# Sheet1.net
KiCad netlist of a schematic drawn in Altium Designer
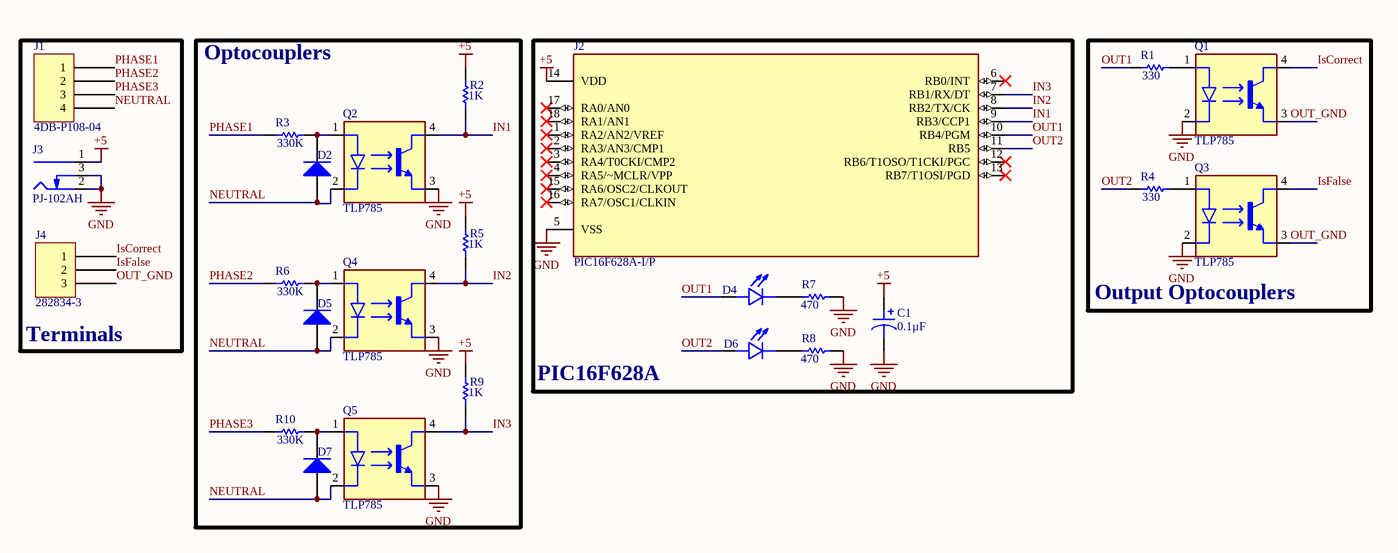
[diagram p0: Sheet1.SchDoc]

(export (version "E")
  (design (tool "Eeschema 10.0.6"))
  (components
    (comp (ref "C1")
      (value "0.1µF")
      (footprint "CAP TH ALUM ELEC D5.00mm S2.00mm H12.00mm")
      (description "CAP ALUM 0.1UF 10% 100V RADIAL")
      (fields (field (name "PART NUMBER") "UKL2A0R1KDD") (field (name "MANUFACTURER") "Nichicon"))
      (libsource (lib "Celestial Altium Library - altium_library") (part "Polarised Capacitor"))
    )
    (comp (ref "D2")
      (value "Diode 1N4007")
      (footprint "DO-41")
      (description "1 Amp General Purpose Rectifier")
      (fields (field (name "PUBLISHER") "Altium Limited"))
      (libsource (lib "Miscellaneous Devices") (part "Diode 1N4007"))
    )
    (comp (ref "D4")
      (value "HLMP-4719-A00B2")
      (footprint "LEDRD254W47D584H1078")
      (description "Yellow 5mm LED LOW CURRENT 2mA R/A T/L")
      (fields (field (name "MF") "Avago"))
      (libsource (lib "5mmLED") (part "HLMP-4719-A00B2"))
    )
    (comp (ref "D5")
      (value "Diode 1N4007")
      (footprint "DO-41")
      (description "1 Amp General Purpose Rectifier")
      (fields (field (name "PUBLISHER") "Altium Limited"))
      (libsource (lib "Miscellaneous Devices") (part "Diode 1N4007"))
    )
    (comp (ref "D6")
      (value "HLMP-4719-A00B2")
      (footprint "LEDRD254W47D584H1078")
      (description "Yellow 5mm LED LOW CURRENT 2mA R/A T/L")
      (fields (field (name "MF") "Avago"))
      (libsource (lib "5mmLED") (part "HLMP-4719-A00B2"))
    )
    (comp (ref "D7")
      (value "Diode 1N4007")
      (footprint "DO-41")
      (description "1 Amp General Purpose Rectifier")
      (fields (field (name "PUBLISHER") "Altium Limited"))
      (libsource (lib "Miscellaneous Devices") (part "Diode 1N4007"))
    )
    (comp (ref "J1")
      (value "4DB-P108-04")
      (footprint "TE 4DB-P108-04")
      (description "CONN BARRIER STRIP 4CIRC 0.325\"")
      (fields (field (name "MANUFACTURER") "TE Connectivity AMP Connectors"))
      (libsource (lib "Celestial Altium Library - altium_library") (part "4 Pin"))
    )
    (comp (ref "J2")
      (value "PIC16F628A-I/P")
      (footprint "DIP254P762X533-18")
      (description "18-Pin 3.5 KB Flash 224 RAM 16 I/O, PIC 16F Series ¦ Microchip Technology Inc. PIC16F628A-I/P")
      (fields (field (name "MF") "Microchip"))
      (libsource (lib "PIC16F628A") (part "PIC16F628A-I/P"))
    )
    (comp (ref "J3")
      (value "PJ-102AH")
      (footprint "CUI PJ-102AH")
      (description "CONN PWR JACK 2X5.5MM SOLDER")
      (fields (field (name "MANUFACTURER") "CUI Devices"))
      (libsource (lib "Celestial Altium Library - altium_library") (part "Barrel Connector"))
    )
    (comp (ref "J4")
      (value "282834-3")
      (footprint "TE 282834-3")
      (description "TERM BLK 3P SIDE ENT 2.54MM PCB")
      (fields (field (name "MANUFACTURER") "TE Connectivity AMP Connectors") (field (name "VOLTAGE") "150V"))
      (libsource (lib "Celestial Altium Library - altium_library") (part "3 Pin"))
    )
    (comp (ref "Q1")
      (value "TLP785")
      (footprint "DIP762W50P254L460H425Q4")
      (description "Optoisolator Transistor Output 5000Vrms 1 Channel 4-DIP")
      (fields (field (name "MF") "Toshiba"))
      (libsource (lib "Optocoupler-TLP785") (part "TLP785"))
    )
    (comp (ref "Q2")
      (value "TLP785")
      (footprint "DIP762W50P254L460H425Q4")
      (description "Optoisolator Transistor Output 5000Vrms 1 Channel 4-DIP")
      (fields (field (name "MF") "Toshiba"))
      (libsource (lib "Optocoupler-TLP785") (part "TLP785"))
    )
    (comp (ref "Q3")
      (value "TLP785")
      (footprint "DIP762W50P254L460H425Q4")
      (description "Optoisolator Transistor Output 5000Vrms 1 Channel 4-DIP")
      (fields (field (name "MF") "Toshiba"))
      (libsource (lib "Optocoupler-TLP785") (part "TLP785"))
    )
    (comp (ref "Q4")
      (value "TLP785")
      (footprint "DIP762W50P254L460H425Q4")
      (description "Optoisolator Transistor Output 5000Vrms 1 Channel 4-DIP")
      (fields (field (name "MF") "Toshiba"))
      (libsource (lib "Optocoupler-TLP785") (part "TLP785"))
    )
    (comp (ref "Q5")
      (value "TLP785")
      (footprint "DIP762W50P254L460H425Q4")
      (description "Optoisolator Transistor Output 5000Vrms 1 Channel 4-DIP")
      (fields (field (name "MF") "Toshiba"))
      (libsource (lib "Optocoupler-TLP785") (part "TLP785"))
    )
    (comp (ref "R1")
      (value "330")
      (footprint "AXIAL-0.3")
      (description "Resistor")
      (fields (field (name "Comment") "Res1") (field (name "PUBLISHER") "Altium Limited"))
      (libsource (lib "Miscellaneous Devices") (part "Res1"))
    )
    (comp (ref "R2")
      (value "1K")
      (footprint "AXIAL-0.3")
      (description "Resistor")
      (fields (field (name "Comment") "Res1") (field (name "PUBLISHER") "Altium Limited"))
      (libsource (lib "Miscellaneous Devices") (part "Res1"))
    )
    (comp (ref "R3")
      (value "330K")
      (footprint "AXIAL-0.3")
      (description "Resistor")
      (fields (field (name "Comment") "Res1") (field (name "PUBLISHER") "Altium Limited"))
      (libsource (lib "Miscellaneous Devices") (part "Res1"))
    )
    (comp (ref "R4")
      (value "330")
      (footprint "AXIAL-0.3")
      (description "Resistor")
      (fields (field (name "Comment") "Res1") (field (name "PUBLISHER") "Altium Limited"))
      (libsource (lib "Miscellaneous Devices") (part "Res1"))
    )
    (comp (ref "R5")
      (value "1K")
      (footprint "AXIAL-0.3")
      (description "Resistor")
      (fields (field (name "Comment") "Res1") (field (name "PUBLISHER") "Altium Limited"))
      (libsource (lib "Miscellaneous Devices") (part "Res1"))
    )
    (comp (ref "R6")
      (value "330K")
      (footprint "AXIAL-0.3")
      (description "Resistor")
      (fields (field (name "Comment") "Res1") (field (name "PUBLISHER") "Altium Limited"))
      (libsource (lib "Miscellaneous Devices") (part "Res1"))
    )
    (comp (ref "R7")
      (value "470")
      (footprint "AXIAL-0.3")
      (description "Resistor")
      (fields (field (name "Comment") "Res1") (field (name "PUBLISHER") "Altium Limited"))
      (libsource (lib "Miscellaneous Devices") (part "Res1"))
    )
    (comp (ref "R8")
      (value "470")
      (footprint "AXIAL-0.3")
      (description "Resistor")
      (fields (field (name "Comment") "Res1") (field (name "PUBLISHER") "Altium Limited"))
      (libsource (lib "Miscellaneous Devices") (part "Res1"))
    )
    (comp (ref "R9")
      (value "1K")
      (footprint "AXIAL-0.3")
      (description "Resistor")
      (fields (field (name "Comment") "Res1") (field (name "PUBLISHER") "Altium Limited"))
      (libsource (lib "Miscellaneous Devices") (part "Res1"))
    )
    (comp (ref "R10")
      (value "330K")
      (footprint "AXIAL-0.3")
      (description "Resistor")
      (fields (field (name "Comment") "Res1") (field (name "PUBLISHER") "Altium Limited"))
      (libsource (lib "Miscellaneous Devices") (part "Res1"))
    )
  )
  (nets
    (net (code "1") (name "+5") (class "Default")
      (node (ref "C1") (pin "1") (pinfunction "1_1") (pintype "passive"))
      (node (ref "J2") (pin "14") (pinfunction "VDD_14") (pintype "power_in"))
      (node (ref "J3") (pin "1") (pinfunction "Centre_1") (pintype "passive"))
      (node (ref "R2") (pin "2") (pinfunction "2_2") (pintype "passive"))
      (node (ref "R5") (pin "2") (pinfunction "2_2") (pintype "passive"))
      (node (ref "R9") (pin "2") (pinfunction "2_2") (pintype "passive"))
    )
    (net (code "2") (name "/IN1") (class "Default")
      (node (ref "J2") (pin "9") (pinfunction "RB3/CCP1_9") (pintype "bidirectional"))
      (node (ref "Q2") (pin "4") (pinfunction "COLLECTOR_4") (pintype "passive"))
      (node (ref "R2") (pin "1") (pinfunction "1_1") (pintype "passive"))
    )
    (net (code "3") (name "/IN2") (class "Default")
      (node (ref "J2") (pin "8") (pinfunction "RB2/TX/CK_8") (pintype "bidirectional"))
      (node (ref "Q4") (pin "4") (pinfunction "COLLECTOR_4") (pintype "passive"))
      (node (ref "R5") (pin "1") (pinfunction "1_1") (pintype "passive"))
    )
    (net (code "4") (name "/IN3") (class "Default")
      (node (ref "J2") (pin "7") (pinfunction "RB1/RX/DT_7") (pintype "bidirectional"))
      (node (ref "Q5") (pin "4") (pinfunction "COLLECTOR_4") (pintype "passive"))
      (node (ref "R9") (pin "1") (pinfunction "1_1") (pintype "passive"))
    )
    (net (code "5") (name "/IsCorrect") (class "Default")
      (node (ref "J4") (pin "1") (pinfunction "1_1") (pintype "passive"))
      (node (ref "Q1") (pin "4") (pinfunction "COLLECTOR_4") (pintype "passive"))
    )
    (net (code "6") (name "/IsFalse") (class "Default")
      (node (ref "J4") (pin "2") (pinfunction "2_2") (pintype "passive"))
      (node (ref "Q3") (pin "4") (pinfunction "COLLECTOR_4") (pintype "passive"))
    )
    (net (code "7") (name "/NEUTRAL") (class "Default")
      (node (ref "D2") (pin "1") (pinfunction "A_1") (pintype "passive"))
      (node (ref "D5") (pin "1") (pinfunction "A_1") (pintype "passive"))
      (node (ref "D7") (pin "1") (pinfunction "A_1") (pintype "passive"))
      (node (ref "J1") (pin "4") (pinfunction "4_4") (pintype "passive"))
      (node (ref "Q2") (pin "2") (pinfunction "CATHODE_2") (pintype "passive"))
      (node (ref "Q4") (pin "2") (pinfunction "CATHODE_2") (pintype "passive"))
      (node (ref "Q5") (pin "2") (pinfunction "CATHODE_2") (pintype "passive"))
    )
    (net (code "8") (name "/OUT1") (class "Default")
      (node (ref "D4") (pin "2") (pinfunction "A_2") (pintype "passive"))
      (node (ref "J2") (pin "10") (pinfunction "RB4/PGM_10") (pintype "bidirectional"))
      (node (ref "R1") (pin "1") (pinfunction "1_1") (pintype "passive"))
    )
    (net (code "9") (name "/OUT2") (class "Default")
      (node (ref "D6") (pin "2") (pinfunction "A_2") (pintype "passive"))
      (node (ref "J2") (pin "11") (pinfunction "RB5_11") (pintype "bidirectional"))
      (node (ref "R4") (pin "1") (pinfunction "1_1") (pintype "passive"))
    )
    (net (code "10") (name "/OUT_GND") (class "Default")
      (node (ref "J4") (pin "3") (pinfunction "3_3") (pintype "passive"))
      (node (ref "Q1") (pin "3") (pinfunction "EMITTER_3") (pintype "passive"))
      (node (ref "Q3") (pin "3") (pinfunction "EMITTER_3") (pintype "passive"))
    )
    (net (code "11") (name "/PHASE1") (class "Default")
      (node (ref "J1") (pin "1") (pinfunction "1_1") (pintype "passive"))
      (node (ref "R3") (pin "1") (pinfunction "1_1") (pintype "passive"))
    )
    (net (code "12") (name "/PHASE2") (class "Default")
      (node (ref "J1") (pin "2") (pinfunction "2_2") (pintype "passive"))
      (node (ref "R6") (pin "1") (pinfunction "1_1") (pintype "passive"))
    )
    (net (code "13") (name "/PHASE3") (class "Default")
      (node (ref "J1") (pin "3") (pinfunction "3_3") (pintype "passive"))
      (node (ref "R10") (pin "1") (pinfunction "1_1") (pintype "passive"))
    )
    (net (code "14") (name "GND") (class "Default")
      (node (ref "C1") (pin "2") (pinfunction "2_2") (pintype "passive"))
      (node (ref "J2") (pin "5") (pinfunction "VSS_5") (pintype "power_in"))
      (node (ref "J3") (pin "2") (pinfunction "Outer_2") (pintype "passive"))
      (node (ref "J3") (pin "3") (pinfunction "SW_3") (pintype "passive"))
      (node (ref "Q1") (pin "2") (pinfunction "CATHODE_2") (pintype "passive"))
      (node (ref "Q2") (pin "3") (pinfunction "EMITTER_3") (pintype "passive"))
      (node (ref "Q3") (pin "2") (pinfunction "CATHODE_2") (pintype "passive"))
      (node (ref "Q4") (pin "3") (pinfunction "EMITTER_3") (pintype "passive"))
      (node (ref "Q5") (pin "3") (pinfunction "EMITTER_3") (pintype "passive"))
      (node (ref "R7") (pin "1") (pinfunction "1_1") (pintype "passive"))
      (node (ref "R8") (pin "1") (pinfunction "1_1") (pintype "passive"))
    )
    (net (code "15") (name "Net-(D2-K)") (class "Default")
      (node (ref "D2") (pin "2") (pinfunction "K_2") (pintype "passive"))
      (node (ref "Q2") (pin "1") (pinfunction "ANODE_1") (pintype "passive"))
      (node (ref "R3") (pin "2") (pinfunction "2_2") (pintype "passive"))
    )
    (net (code "16") (name "Net-(D4-C)") (class "Default")
      (node (ref "D4") (pin "1") (pinfunction "C_1") (pintype "passive"))
      (node (ref "R7") (pin "2") (pinfunction "2_2") (pintype "passive"))
    )
    (net (code "17") (name "Net-(D5-K)") (class "Default")
      (node (ref "D5") (pin "2") (pinfunction "K_2") (pintype "passive"))
      (node (ref "Q4") (pin "1") (pinfunction "ANODE_1") (pintype "passive"))
      (node (ref "R6") (pin "2") (pinfunction "2_2") (pintype "passive"))
    )
    (net (code "18") (name "Net-(D6-C)") (class "Default")
      (node (ref "D6") (pin "1") (pinfunction "C_1") (pintype "passive"))
      (node (ref "R8") (pin "2") (pinfunction "2_2") (pintype "passive"))
    )
    (net (code "19") (name "Net-(D7-K)") (class "Default")
      (node (ref "D7") (pin "2") (pinfunction "K_2") (pintype "passive"))
      (node (ref "Q5") (pin "1") (pinfunction "ANODE_1") (pintype "passive"))
      (node (ref "R10") (pin "2") (pinfunction "2_2") (pintype "passive"))
    )
    (net (code "20") (name "Net-(Q1-ANODE)") (class "Default")
      (node (ref "Q1") (pin "1") (pinfunction "ANODE_1") (pintype "passive"))
      (node (ref "R1") (pin "2") (pinfunction "2_2") (pintype "passive"))
    )
    (net (code "21") (name "Net-(Q3-ANODE)") (class "Default")
      (node (ref "Q3") (pin "1") (pinfunction "ANODE_1") (pintype "passive"))
      (node (ref "R4") (pin "2") (pinfunction "2_2") (pintype "passive"))
    )
    (net (code "22") (name "unconnected-(J2-RA0{slash}AN0-Pad17)") (class "Default")
      (node (ref "J2") (pin "17") (pinfunction "RA0/AN0_17") (pintype "bidirectional+no_connect"))
    )
    (net (code "23") (name "unconnected-(J2-RA1{slash}AN1-Pad18)") (class "Default")
      (node (ref "J2") (pin "18") (pinfunction "RA1/AN1_18") (pintype "bidirectional+no_connect"))
    )
    (net (code "24") (name "unconnected-(J2-RA2{slash}AN2{slash}VREF-Pad1)") (class "Default")
      (node (ref "J2") (pin "1") (pinfunction "RA2/AN2/VREF_1") (pintype "bidirectional+no_connect"))
    )
    (net (code "25") (name "unconnected-(J2-RA3{slash}AN3{slash}CMP1-Pad2)") (class "Default")
      (node (ref "J2") (pin "2") (pinfunction "RA3/AN3/CMP1_2") (pintype "bidirectional+no_connect"))
    )
    (net (code "26") (name "unconnected-(J2-RA4{slash}T0CKI{slash}CMP2-Pad3)") (class "Default")
      (node (ref "J2") (pin "3") (pinfunction "RA4/T0CKI/CMP2_3") (pintype "bidirectional+no_connect"))
    )
    (net (code "27") (name "unconnected-(J2-RA5{slash}~MCLR{slash}VPP-Pad4)") (class "Default")
      (node (ref "J2") (pin "4") (pinfunction "RA5/~MCLR/VPP_4") (pintype "bidirectional+no_connect"))
    )
    (net (code "28") (name "unconnected-(J2-RA6{slash}OSC2{slash}CLKOUT-Pad15)") (class "Default")
      (node (ref "J2") (pin "15") (pinfunction "RA6/OSC2/CLKOUT_15") (pintype "bidirectional+no_connect"))
    )
    (net (code "29") (name "unconnected-(J2-RA7{slash}OSC1{slash}CLKIN-Pad16)") (class "Default")
      (node (ref "J2") (pin "16") (pinfunction "RA7/OSC1/CLKIN_16") (pintype "bidirectional+no_connect"))
    )
    (net (code "30") (name "unconnected-(J2-RB0{slash}INT-Pad6)") (class "Default")
      (node (ref "J2") (pin "6") (pinfunction "RB0/INT_6") (pintype "bidirectional+no_connect"))
    )
    (net (code "31") (name "unconnected-(J2-RB6{slash}T1OSO{slash}T1CKI{slash}PGC-Pad12)") (class "Default")
      (node (ref "J2") (pin "12") (pinfunction "RB6/T1OSO/T1CKI/PGC_12") (pintype "bidirectional+no_connect"))
    )
    (net (code "32") (name "unconnected-(J2-RB7{slash}T1OSI{slash}PGD-Pad13)") (class "Default")
      (node (ref "J2") (pin "13") (pinfunction "RB7/T1OSI/PGD_13") (pintype "bidirectional+no_connect"))
    )
  )
)
